# ConduinoBNC-V03V01.net
KiCad netlist of a schematic drawn in EAGLE
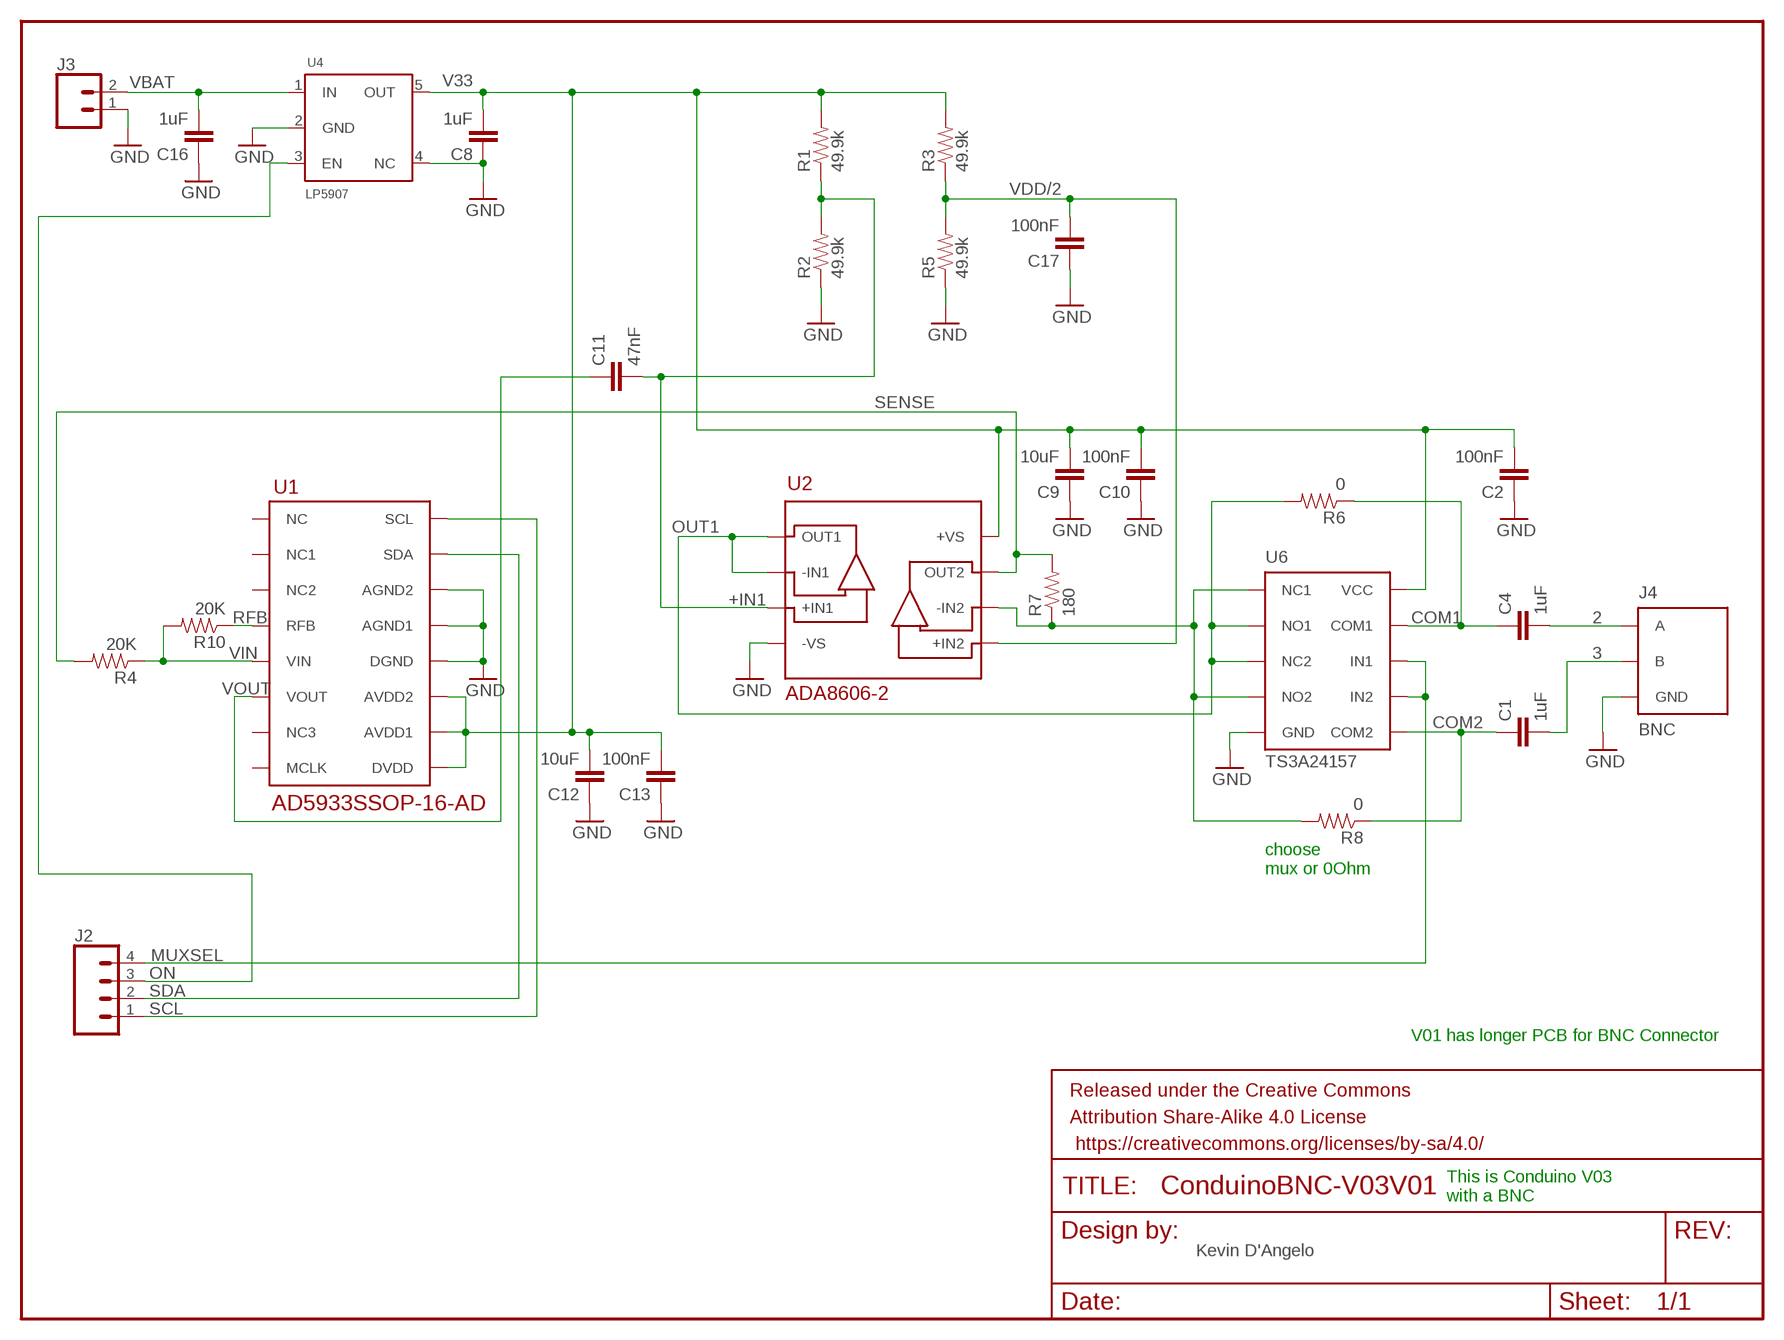
[diagram p0: schematic, sheet 1]

(export (version "E")
  (design (tool "Eeschema 10.0.6"))
  (components
    (comp (ref "C1")
      (value "1uF")
      (footprint "eagle-import:0603-CAP")
      (libsource (lib "eagle-import") (part "CAP0603-CAP"))
    )
    (comp (ref "C2")
      (value "100nF")
      (footprint "eagle-import:0603-CAP")
      (libsource (lib "eagle-import") (part "CAP0603-CAP"))
    )
    (comp (ref "C4")
      (value "1uF")
      (footprint "eagle-import:0603-CAP")
      (libsource (lib "eagle-import") (part "CAP0603-CAP"))
    )
    (comp (ref "C8")
      (value "1uF")
      (footprint "eagle-import:0603-CAP")
      (libsource (lib "eagle-import") (part "CAP0603-CAP"))
    )
    (comp (ref "C9")
      (value "10uF")
      (footprint "eagle-import:0603-CAP")
      (libsource (lib "eagle-import") (part "CAP0603-CAP"))
    )
    (comp (ref "C10")
      (value "100nF")
      (footprint "eagle-import:0603-CAP")
      (libsource (lib "eagle-import") (part "CAP0603-CAP"))
    )
    (comp (ref "C11")
      (value "47nF")
      (footprint "eagle-import:0603-CAP")
      (libsource (lib "eagle-import") (part "CAP0603-CAP"))
    )
    (comp (ref "C12")
      (value "10uF")
      (footprint "eagle-import:0603-CAP")
      (libsource (lib "eagle-import") (part "CAP0603-CAP"))
    )
    (comp (ref "C13")
      (value "100nF")
      (footprint "eagle-import:0603-CAP")
      (libsource (lib "eagle-import") (part "CAP0603-CAP"))
    )
    (comp (ref "C16")
      (value "1uF")
      (footprint "eagle-import:0603-CAP")
      (libsource (lib "eagle-import") (part "CAP0603-CAP"))
    )
    (comp (ref "C17")
      (value "100nF")
      (footprint "eagle-import:0603-CAP")
      (libsource (lib "eagle-import") (part "CAP0603-CAP"))
    )
    (comp (ref "FRAME1")
      (value "FRAME-LETTER")
      (footprint "eagle-import:CREATIVE_COMMONS")
      (libsource (lib "eagle-import") (part "FRAME-LETTER"))
    )
    (comp (ref "J2")
      (value "CONN_041X04_NO_SILK")
      (footprint "eagle-import:1X04_NO_SILK")
      (libsource (lib "eagle-import") (part "CONN_041X04_NO_SILK"))
    )
    (comp (ref "J3")
      (value "CONN_021X02_NO_SILK")
      (footprint "eagle-import:1X02_NO_SILK")
      (libsource (lib "eagle-import") (part "CONN_021X02_NO_SILK"))
    )
    (comp (ref "J4")
      (value "BNC")
      (footprint "eagle-import:BNC")
      (libsource (lib "eagle-import") (part "BNC"))
    )
    (comp (ref "R1")
      (value "49.9k")
      (footprint "eagle-import:0603-RES")
      (libsource (lib "eagle-import") (part "RESISTOR0603-RES"))
    )
    (comp (ref "R2")
      (value "49.9k")
      (footprint "eagle-import:0603-RES")
      (libsource (lib "eagle-import") (part "RESISTOR0603-RES"))
    )
    (comp (ref "R3")
      (value "49.9k")
      (footprint "eagle-import:0603-RES")
      (libsource (lib "eagle-import") (part "RESISTOR0603-RES"))
    )
    (comp (ref "R4")
      (value "20K")
      (footprint "eagle-import:0603-RES")
      (libsource (lib "eagle-import") (part "RESISTOR0603-RES"))
    )
    (comp (ref "R5")
      (value "49.9k")
      (footprint "eagle-import:0603-RES")
      (libsource (lib "eagle-import") (part "RESISTOR0603-RES"))
    )
    (comp (ref "R6")
      (value "0")
      (footprint "eagle-import:0603-RES")
      (libsource (lib "eagle-import") (part "RESISTOR0603-RES"))
    )
    (comp (ref "R7")
      (value "180")
      (footprint "eagle-import:0603-RES")
      (libsource (lib "eagle-import") (part "RESISTOR0603-RES"))
    )
    (comp (ref "R8")
      (value "0")
      (footprint "eagle-import:0603-RES")
      (libsource (lib "eagle-import") (part "RESISTOR0603-RES"))
    )
    (comp (ref "R10")
      (value "20K")
      (footprint "eagle-import:0603-RES")
      (libsource (lib "eagle-import") (part "RESISTOR0603-RES"))
    )
    (comp (ref "U1")
      (value "AD5933SSOP-16-AD")
      (footprint "eagle-import:SSOP-16-AD")
      (libsource (lib "eagle-import") (part "AD5933SSOP-16-AD"))
    )
    (comp (ref "U2")
      (value "ADA8606-2")
      (footprint "eagle-import:SOIC_N")
      (libsource (lib "eagle-import") (part "ADA8606-2"))
    )
    (comp (ref "U4")
      (value "LP5907")
      (footprint "eagle-import:SOT23-5L")
      (libsource (lib "eagle-import") (part "LP5907"))
    )
    (comp (ref "U6")
      (value "TS3A24157")
      (footprint "eagle-import:VSSOP-10")
      (libsource (lib "eagle-import") (part "TS3A24157"))
    )
  )
  (nets
    (net (code "1") (name "/+IN1") (class "Default")
      (node (ref "C11") (pin "2") (pinfunction "2_2") (pintype "passive"))
      (node (ref "R1") (pin "1") (pinfunction "1_1") (pintype "passive"))
      (node (ref "R2") (pin "2") (pinfunction "2_2") (pintype "passive"))
      (node (ref "U2") (pin "P$3") (pinfunction "+IN1_P$3") (pintype "bidirectional"))
    )
    (net (code "2") (name "/2") (class "Default")
      (node (ref "C4") (pin "2") (pinfunction "2_2") (pintype "passive"))
      (node (ref "J4") (pin "P$1") (pinfunction "A_P$1") (pintype "bidirectional"))
    )
    (net (code "3") (name "/3") (class "Default")
      (node (ref "C1") (pin "2") (pinfunction "2_2") (pintype "passive"))
      (node (ref "J4") (pin "P$2") (pinfunction "B_P$2") (pintype "bidirectional"))
    )
    (net (code "4") (name "/COM1") (class "Default")
      (node (ref "C4") (pin "1") (pinfunction "1_1") (pintype "passive"))
      (node (ref "R6") (pin "1") (pinfunction "1_1") (pintype "passive"))
      (node (ref "U6") (pin "P$9") (pinfunction "COM1_P$9") (pintype "bidirectional"))
    )
    (net (code "5") (name "/COM2") (class "Default")
      (node (ref "C1") (pin "1") (pinfunction "1_1") (pintype "passive"))
      (node (ref "R8") (pin "1") (pinfunction "1_1") (pintype "passive"))
      (node (ref "U6") (pin "P$6") (pinfunction "COM2_P$6") (pintype "bidirectional"))
    )
    (net (code "6") (name "/MUXSEL") (class "Default")
      (node (ref "J2") (pin "4") (pinfunction "4_4") (pintype "passive"))
      (node (ref "U6") (pin "P$7") (pinfunction "IN2_P$7") (pintype "bidirectional"))
      (node (ref "U6") (pin "P$8") (pinfunction "IN1_P$8") (pintype "bidirectional"))
    )
    (net (code "7") (name "/ON") (class "Default")
      (node (ref "J2") (pin "3") (pinfunction "3_3") (pintype "passive"))
      (node (ref "U4") (pin "3") (pinfunction "EN_3") (pintype "input"))
    )
    (net (code "8") (name "/OUT1") (class "Default")
      (node (ref "R6") (pin "2") (pinfunction "2_2") (pintype "passive"))
      (node (ref "U2") (pin "P$1") (pinfunction "OUT1_P$1") (pintype "bidirectional"))
      (node (ref "U2") (pin "P$2") (pinfunction "-IN1_P$2") (pintype "bidirectional"))
      (node (ref "U6") (pin "P$2") (pinfunction "NO1_P$2") (pintype "bidirectional"))
      (node (ref "U6") (pin "P$3") (pinfunction "NC2_P$3") (pintype "bidirectional"))
    )
    (net (code "9") (name "/RFB") (class "Default")
      (node (ref "R10") (pin "1") (pinfunction "1_1") (pintype "passive"))
      (node (ref "U1") (pin "P$4") (pinfunction "RFB_P$4") (pintype "passive"))
    )
    (net (code "10") (name "/SCL") (class "Default")
      (node (ref "J2") (pin "1") (pinfunction "1_1") (pintype "passive"))
      (node (ref "U1") (pin "P$16") (pinfunction "SCL_P$16") (pintype "passive"))
    )
    (net (code "11") (name "/SDA") (class "Default")
      (node (ref "J2") (pin "2") (pinfunction "2_2") (pintype "passive"))
      (node (ref "U1") (pin "P$15") (pinfunction "SDA_P$15") (pintype "passive"))
    )
    (net (code "12") (name "/SENSE") (class "Default")
      (node (ref "R4") (pin "2") (pinfunction "2_2") (pintype "passive"))
      (node (ref "R7") (pin "2") (pinfunction "2_2") (pintype "passive"))
      (node (ref "U2") (pin "P$7") (pinfunction "OUT2_P$7") (pintype "bidirectional"))
    )
    (net (code "13") (name "/V33") (class "Default")
      (node (ref "C10") (pin "2") (pinfunction "2_2") (pintype "passive"))
      (node (ref "C12") (pin "2") (pinfunction "2_2") (pintype "passive"))
      (node (ref "C13") (pin "2") (pinfunction "2_2") (pintype "passive"))
      (node (ref "C2") (pin "2") (pinfunction "2_2") (pintype "passive"))
      (node (ref "C8") (pin "2") (pinfunction "2_2") (pintype "passive"))
      (node (ref "C9") (pin "2") (pinfunction "2_2") (pintype "passive"))
      (node (ref "R1") (pin "2") (pinfunction "2_2") (pintype "passive"))
      (node (ref "R3") (pin "2") (pinfunction "2_2") (pintype "passive"))
      (node (ref "U1") (pin "P$10") (pinfunction "AVDD1_P$10") (pintype "passive"))
      (node (ref "U1") (pin "P$11") (pinfunction "AVDD2_P$11") (pintype "passive"))
      (node (ref "U1") (pin "P$9") (pinfunction "DVDD_P$9") (pintype "passive"))
      (node (ref "U2") (pin "P$8") (pinfunction "+VS_P$8") (pintype "bidirectional"))
      (node (ref "U4") (pin "5") (pinfunction "OUT_5") (pintype "power_in"))
      (node (ref "U6") (pin "P$10") (pinfunction "VCC_P$10") (pintype "bidirectional"))
    )
    (net (code "14") (name "/VBAT") (class "Default")
      (node (ref "C16") (pin "2") (pinfunction "2_2") (pintype "passive"))
      (node (ref "J3") (pin "2") (pinfunction "2_2") (pintype "passive"))
      (node (ref "U4") (pin "1") (pinfunction "IN_1") (pintype "power_in"))
    )
    (net (code "15") (name "/VDD{slash}2") (class "Default")
      (node (ref "C17") (pin "2") (pinfunction "2_2") (pintype "passive"))
      (node (ref "R3") (pin "1") (pinfunction "1_1") (pintype "passive"))
      (node (ref "R5") (pin "2") (pinfunction "2_2") (pintype "passive"))
      (node (ref "U2") (pin "P$5") (pinfunction "+IN2_P$5") (pintype "bidirectional"))
    )
    (net (code "16") (name "/VIN") (class "Default")
      (node (ref "R10") (pin "2") (pinfunction "2_2") (pintype "passive"))
      (node (ref "R4") (pin "1") (pinfunction "1_1") (pintype "passive"))
      (node (ref "U1") (pin "P$5") (pinfunction "VIN_P$5") (pintype "passive"))
    )
    (net (code "17") (name "/VOUT") (class "Default")
      (node (ref "C11") (pin "1") (pinfunction "1_1") (pintype "passive"))
      (node (ref "U1") (pin "P$6") (pinfunction "VOUT_P$6") (pintype "passive"))
    )
    (net (code "18") (name "GND") (class "Default")
      (node (ref "C10") (pin "1") (pinfunction "1_1") (pintype "passive"))
      (node (ref "C12") (pin "1") (pinfunction "1_1") (pintype "passive"))
      (node (ref "C13") (pin "1") (pinfunction "1_1") (pintype "passive"))
      (node (ref "C16") (pin "1") (pinfunction "1_1") (pintype "passive"))
      (node (ref "C17") (pin "1") (pinfunction "1_1") (pintype "passive"))
      (node (ref "C2") (pin "1") (pinfunction "1_1") (pintype "passive"))
      (node (ref "C8") (pin "1") (pinfunction "1_1") (pintype "passive"))
      (node (ref "C9") (pin "1") (pinfunction "1_1") (pintype "passive"))
      (node (ref "J3") (pin "1") (pinfunction "1_1") (pintype "passive"))
      (node (ref "J4") (pin "P$3") (pinfunction "GND_P$3") (pintype "bidirectional"))
      (node (ref "J4") (pin "P$4") (pinfunction "GND_P$4") (pintype "bidirectional"))
      (node (ref "R2") (pin "1") (pinfunction "1_1") (pintype "passive"))
      (node (ref "R5") (pin "1") (pinfunction "1_1") (pintype "passive"))
      (node (ref "U1") (pin "P$12") (pinfunction "DGND_P$12") (pintype "passive"))
      (node (ref "U1") (pin "P$13") (pinfunction "AGND1_P$13") (pintype "passive"))
      (node (ref "U1") (pin "P$14") (pinfunction "AGND2_P$14") (pintype "passive"))
      (node (ref "U2") (pin "P$4") (pinfunction "-VS_P$4") (pintype "bidirectional"))
      (node (ref "U4") (pin "2") (pinfunction "GND_2") (pintype "power_in"))
      (node (ref "U4") (pin "4") (pinfunction "NC_4") (pintype "bidirectional"))
      (node (ref "U6") (pin "P$5") (pinfunction "GND_P$5") (pintype "bidirectional"))
    )
    (net (code "19") (name "Net-(U2--IN2)") (class "Default")
      (node (ref "R7") (pin "1") (pinfunction "1_1") (pintype "passive"))
      (node (ref "R8") (pin "2") (pinfunction "2_2") (pintype "passive"))
      (node (ref "U2") (pin "P$6") (pinfunction "-IN2_P$6") (pintype "bidirectional"))
      (node (ref "U6") (pin "P$1") (pinfunction "NC1_P$1") (pintype "bidirectional"))
      (node (ref "U6") (pin "P$4") (pinfunction "NO2_P$4") (pintype "bidirectional"))
    )
    (net (code "20") (name "unconnected-(U1-MCLK-PadP$8)") (class "Default")
      (node (ref "U1") (pin "P$8") (pinfunction "MCLK_P$8") (pintype "passive"))
    )
    (net (code "21") (name "unconnected-(U1-NC-PadP$1)") (class "Default")
      (node (ref "U1") (pin "P$1") (pinfunction "NC_P$1") (pintype "passive"))
    )
    (net (code "22") (name "unconnected-(U1-NC1-PadP$2)") (class "Default")
      (node (ref "U1") (pin "P$2") (pinfunction "NC1_P$2") (pintype "passive"))
    )
    (net (code "23") (name "unconnected-(U1-NC2-PadP$3)") (class "Default")
      (node (ref "U1") (pin "P$3") (pinfunction "NC2_P$3") (pintype "passive"))
    )
    (net (code "24") (name "unconnected-(U1-NC3-PadP$7)") (class "Default")
      (node (ref "U1") (pin "P$7") (pinfunction "NC3_P$7") (pintype "passive"))
    )
  )
)
